# current_sensor.net
KiCad netlist of a schematic drawn in Altium Designer
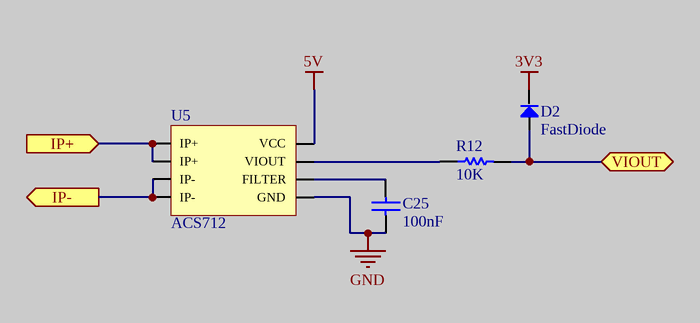
[diagram p0: current_sensor.SchDoc]

(export (version "E")
  (design (tool "Eeschema 10.0.6"))
  (components
    (comp (ref "C25")
      (value "100nF")
      (footprint "CAPC0603")
      (description "Capacitor")
      (fields (field (name "PUBLISHER") "Altium Limited"))
      (libsource (lib "eLIB") (part "Capacitor"))
    )
    (comp (ref "D2")
      (value "FastDiode")
      (footprint "FastDiode")
      (fields (field (name "PUBLISHER") "Altium Limited"))
      (libsource (lib "eLIB") (part "FastDiode"))
    )
    (comp (ref "R12")
      (value "10K")
      (footprint "RESC0603")
      (description "0603,0.1W")
      (fields (field (name "PUBLISHER") "Altium Limited"))
      (libsource (lib "eLIB") (part "Resistor"))
    )
    (comp (ref "U5")
      (value "ACS712")
      (footprint "ACS712")
      (description "Sensing Current")
      (libsource (lib "eLIB") (part "ACS712"))
    )
  )
  (nets
    (net (code "1") (name "/IP+") (class "Default")
      (node (ref "U5") (pin "1") (pinfunction "IP+_1") (pintype "passive"))
      (node (ref "U5") (pin "2") (pinfunction "IP+_2") (pintype "passive"))
    )
    (net (code "2") (name "/IP-") (class "Default")
      (node (ref "U5") (pin "3") (pinfunction "IP-_3") (pintype "passive"))
      (node (ref "U5") (pin "4") (pinfunction "IP-_4") (pintype "passive"))
    )
    (net (code "3") (name "/VIOUT") (class "Default")
      (node (ref "D2") (pin "1") (pinfunction "A_1") (pintype "passive"))
      (node (ref "R12") (pin "2") (pinfunction "2_2") (pintype "passive"))
    )
    (net (code "4") (name "3V3") (class "Default")
      (node (ref "D2") (pin "2") (pinfunction "K_2") (pintype "passive"))
    )
    (net (code "5") (name "5V") (class "Default")
      (node (ref "U5") (pin "8") (pinfunction "VCC_8") (pintype "passive"))
    )
    (net (code "6") (name "GND") (class "Default")
      (node (ref "C25") (pin "1") (pinfunction "1_1") (pintype "passive"))
      (node (ref "U5") (pin "5") (pinfunction "GND_5") (pintype "passive"))
    )
    (net (code "7") (name "Net-(U5-FILTER)") (class "Default")
      (node (ref "C25") (pin "2") (pinfunction "2_2") (pintype "passive"))
      (node (ref "U5") (pin "6") (pinfunction "FILTER_6") (pintype "passive"))
    )
    (net (code "8") (name "Net-(U5-VIOUT)") (class "Default")
      (node (ref "R12") (pin "1") (pinfunction "1_1") (pintype "passive"))
      (node (ref "U5") (pin "7") (pinfunction "VIOUT_7") (pintype "passive"))
    )
  )
)
